# RC_Transmitter_TX_v43.net
KiCad netlist of a schematic drawn in EAGLE
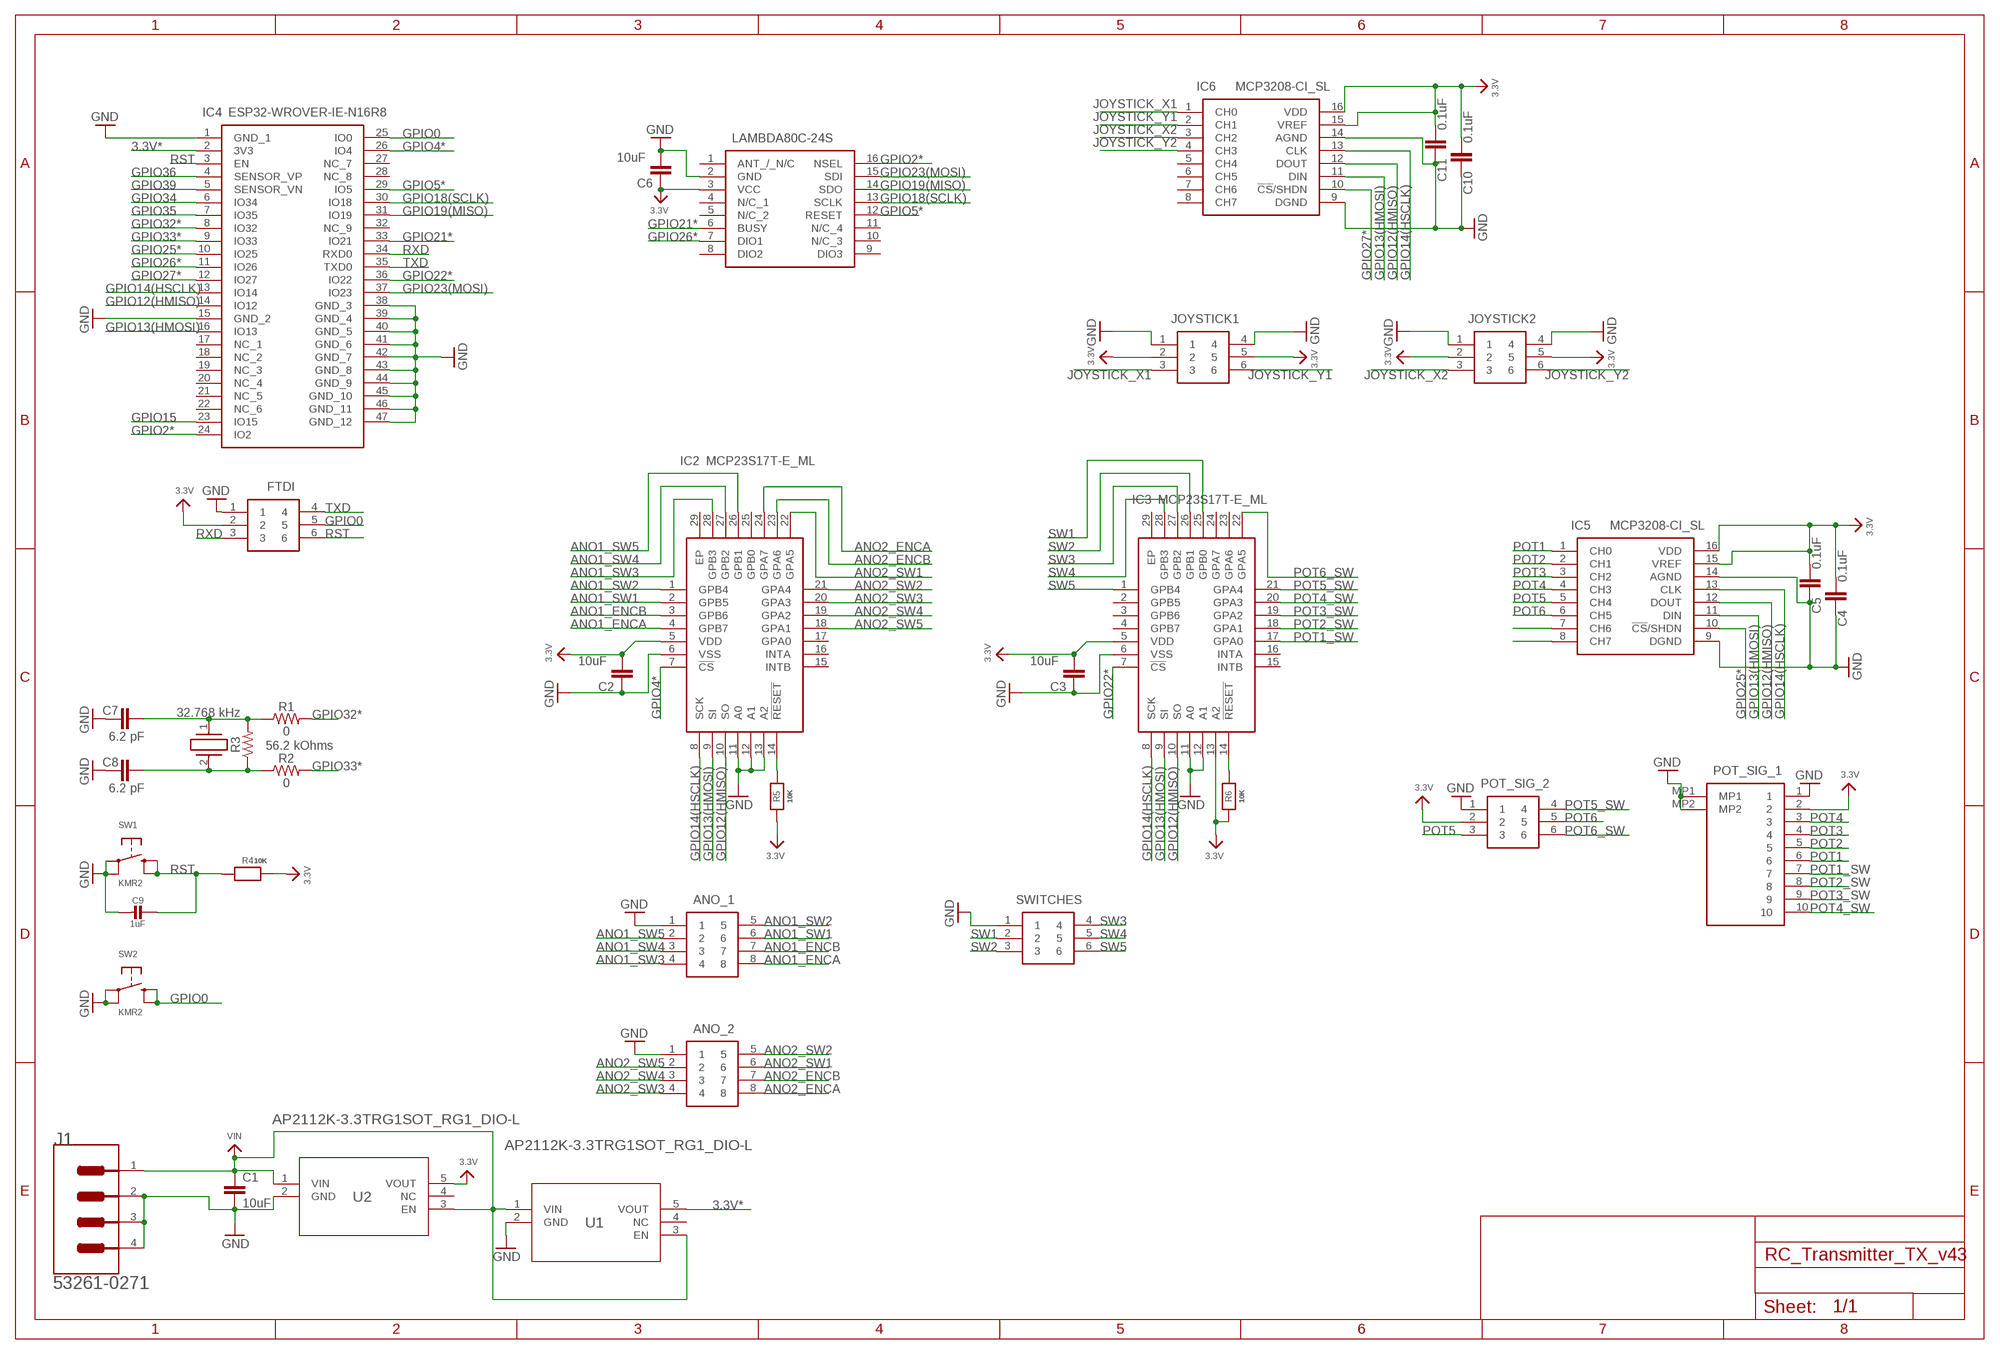
[diagram p0: schematic, sheet 1]

(export (version "E")
  (design (tool "Eeschema 10.0.6"))
  (components
    (comp (ref "ANO_1")
      (value "0532610871")
      (footprint "eagle-import:53261-0871")
      (libsource (lib "eagle-import") (part "0532610871"))
    )
    (comp (ref "ANO_2")
      (value "0532610871")
      (footprint "eagle-import:53261-0871")
      (libsource (lib "eagle-import") (part "0532610871"))
    )
    (comp (ref "C1")
      (value "10uF")
      (footprint "eagle-import:0805")
      (libsource (lib "eagle-import") (part "10UF-0805-10V-10%"))
    )
    (comp (ref "C2")
      (value "10uF")
      (footprint "eagle-import:0805")
      (libsource (lib "eagle-import") (part "10UF-0805-10V-10%"))
    )
    (comp (ref "C3")
      (value "10uF")
      (footprint "eagle-import:0805")
      (libsource (lib "eagle-import") (part "10UF-0805-10V-10%"))
    )
    (comp (ref "C4")
      (value "0.1uF")
      (footprint "eagle-import:0805")
      (libsource (lib "eagle-import") (part "10UF-0805-10V-10%"))
    )
    (comp (ref "C5")
      (value "0.1uF")
      (footprint "eagle-import:0805")
      (libsource (lib "eagle-import") (part "10UF-0805-10V-10%"))
    )
    (comp (ref "C6")
      (value "10uF")
      (footprint "eagle-import:0805")
      (libsource (lib "eagle-import") (part "10UF-0805-10V-10%"))
    )
    (comp (ref "C7")
      (value "6.2 pF")
      (footprint "eagle-import:CAPC2012X110")
      (libsource (lib "eagle-import") (part "CCHIP-0805(2012-METRIC)_"))
    )
    (comp (ref "C8")
      (value "6.2 pF")
      (footprint "eagle-import:CAPC2012X110")
      (libsource (lib "eagle-import") (part "CCHIP-0805(2012-METRIC)_"))
    )
    (comp (ref "C9")
      (value "1uF")
      (footprint "eagle-import:0805-NO")
      (libsource (lib "eagle-import") (part "CAP_CERAMIC0805-NOOUTLINE"))
    )
    (comp (ref "C10")
      (value "0.1uF")
      (footprint "eagle-import:0805")
      (libsource (lib "eagle-import") (part "10UF-0805-10V-10%"))
    )
    (comp (ref "C11")
      (value "0.1uF")
      (footprint "eagle-import:0805")
      (libsource (lib "eagle-import") (part "10UF-0805-10V-10%"))
    )
    (comp (ref "CRYSTAL")
      (value "32.768 kHz")
      (footprint "eagle-import:ECX327CDX1293")
      (fields
        (field (name "ARROW_PART_NUMBER") "ECX-.327-CDX-1293")
        (field (name "MOUSER_PART_NUMBER") "520-ECX-.327CDX-1293")
        (field (name "ARROW_PART_NUMBER_1") "Crystal")
      )
      (libsource (lib "eagle-import") (part "ECX-.327-CDX-1293"))
    )
    (comp (ref "FTDI")
      (value "0532610671")
      (footprint "eagle-import:0532610671")
      (libsource (lib "eagle-import") (part "0532610671"))
    )
    (comp (ref "IC1")
      (value "LAMBDA80C-24S")
      (footprint "eagle-import:LAMBDA80C24S")
      (fields (field (name "MOUSER_PART_NUMBER") "223-LAMBDA80C-24S"))
      (libsource (lib "eagle-import") (part "LAMBDA80C-24S"))
    )
    (comp (ref "IC2")
      (value "MCP23S17T-E_ML")
      (footprint "eagle-import:QFN65P600X600X100-29N")
      (fields
        (field (name "ARROW_PART_NUMBER") "MCP23S17T-E/ML")
        (field (name "MOUSER_PART_NUMBER") "579-MCP23S17T-E/ML")
      )
      (libsource (lib "eagle-import") (part "MCP23S17T-E_ML"))
    )
    (comp (ref "IC3")
      (value "MCP23S17T-E_ML")
      (footprint "eagle-import:QFN65P600X600X100-29N")
      (fields
        (field (name "ARROW_PART_NUMBER") "MCP23S17T-E/ML")
        (field (name "MOUSER_PART_NUMBER") "579-MCP23S17T-E/ML")
      )
      (libsource (lib "eagle-import") (part "MCP23S17T-E_ML"))
    )
    (comp (ref "IC4")
      (value "ESP32-WROVER-IE-N16R8")
      (footprint "eagle-import:ESP32WROVERIEN16R8")
      (fields
        (field (name "MANUFACTURER_PART_NUMBER") "ESP32-Wrover-IE-N16R8")
        (field (name "MOUSER_PART_NUMBER") "356-ESP32WRVIE2864UC")
      )
      (libsource (lib "eagle-import") (part "ESP32-WROVER-IE-N16R8"))
    )
    (comp (ref "IC5")
      (value "MCP3208-CI_SL")
      (footprint "eagle-import:SOIC127P600X175-16N")
      (fields
        (field (name "ARROW_PART_NUMBER") "MCP3208-CI/SL")
        (field (name "MOUSER_PART_NUMBER") "579-MCP3208CISL")
      )
      (libsource (lib "eagle-import") (part "MCP3208-CI_SL"))
    )
    (comp (ref "IC6")
      (value "MCP3208-CI_SL")
      (footprint "eagle-import:SOIC127P600X175-16N")
      (fields
        (field (name "ARROW_PART_NUMBER") "MCP3208-CI/SL")
        (field (name "MOUSER_PART_NUMBER") "579-MCP3208CISL")
      )
      (libsource (lib "eagle-import") (part "MCP3208-CI_SL"))
    )
    (comp (ref "J1")
      (value "MOLEX_53261-0271MOLEX_53261-0271_0_0")
      (footprint "eagle-import:MOLEX_53261-0271_0")
      (fields
        (field (name "DIGIKEY_PART_NUMBER") "WM7620CT-ND")
        (field (name "MF") "Molex")
        (field (name "MOUSER_PART_NUMBER") "538-53261-0271")
      )
      (libsource (lib "eagle-import") (part "MOLEX_53261-0271MOLEX_53261-0271_0_0"))
    )
    (comp (ref "JOYSTICK1")
      (value "0532610671")
      (footprint "eagle-import:0532610671")
      (libsource (lib "eagle-import") (part "0532610671"))
    )
    (comp (ref "JOYSTICK2")
      (value "0532610671")
      (footprint "eagle-import:0532610671")
      (libsource (lib "eagle-import") (part "0532610671"))
    )
    (comp (ref "POT_SIG_1")
      (value "0532611071")
      (footprint "eagle-import:0532611071")
      (libsource (lib "eagle-import") (part "0532611071"))
    )
    (comp (ref "POT_SIG_2")
      (value "0532610671")
      (footprint "eagle-import:0532610671")
      (libsource (lib "eagle-import") (part "0532610671"))
    )
    (comp (ref "R1")
      (value "0")
      (footprint "eagle-import:0603")
      (libsource (lib "eagle-import") (part "0OHM-0603-1/10W-5%"))
    )
    (comp (ref "R2")
      (value "0")
      (footprint "eagle-import:0603")
      (libsource (lib "eagle-import") (part "0OHM-0603-1/10W-5%"))
    )
    (comp (ref "R3")
      (value "56.2 kOhms")
      (footprint "eagle-import:0603")
      (libsource (lib "eagle-import") (part "0OHM-0603-1/10W-5%"))
    )
    (comp (ref "R4")
      (value "10K")
      (footprint "eagle-import:_0805")
      (libsource (lib "eagle-import") (part "RESISTOR_0805"))
    )
    (comp (ref "R5")
      (value "10K")
      (footprint "eagle-import:_0805")
      (libsource (lib "eagle-import") (part "RESISTOR_0805"))
    )
    (comp (ref "R6")
      (value "10K")
      (footprint "eagle-import:_0805")
      (libsource (lib "eagle-import") (part "RESISTOR_0805"))
    )
    (comp (ref "SW1")
      (value "KMR2")
      (footprint "eagle-import:BTN_KMR2_4.6X2.8")
      (libsource (lib "eagle-import") (part "SWITCH_TACT_SMT4.6X2.8"))
    )
    (comp (ref "SW2")
      (value "KMR2")
      (footprint "eagle-import:BTN_KMR2_4.6X2.8")
      (libsource (lib "eagle-import") (part "SWITCH_TACT_SMT4.6X2.8"))
    )
    (comp (ref "SWITCHES")
      (value "0532610671")
      (footprint "eagle-import:0532610671")
      (libsource (lib "eagle-import") (part "0532610671"))
    )
    (comp (ref "U1")
      (value "AP2112K-3.3TRG1SOT_RG1_DIO-L")
      (footprint "eagle-import:SOT_RG1_DIO-L")
      (fields
        (field (name "MANUFACTURER_PART_NUMBER") "AP2112K-3.3TRG1")
        (field (name "COPYRIGHT") "Copyright (C) 2023 Ultra Librarian. All rights reserved.")
      )
      (libsource (lib "eagle-import") (part "AP2112K-3.3TRG1SOT_RG1_DIO-L"))
    )
    (comp (ref "U2")
      (value "AP2112K-3.3TRG1SOT_RG1_DIO-L")
      (footprint "eagle-import:SOT_RG1_DIO-L")
      (fields
        (field (name "MANUFACTURER_PART_NUMBER") "AP2112K-3.3TRG1")
        (field (name "COPYRIGHT") "Copyright (C) 2023 Ultra Librarian. All rights reserved.")
      )
      (libsource (lib "eagle-import") (part "AP2112K-3.3TRG1SOT_RG1_DIO-L"))
    )
  )
  (nets
    (net (code "1") (name "/3.3V*") (class "Default")
      (node (ref "IC4") (pin "2") (pinfunction "3V3_2") (pintype "bidirectional"))
      (node (ref "U1") (pin "5") (pinfunction "VOUT_5") (pintype "passive"))
    )
    (net (code "2") (name "/ANO1_ENCA") (class "Default")
      (node (ref "ANO_1") (pin "8") (pinfunction "8_8") (pintype "bidirectional"))
      (node (ref "IC2") (pin "4") (pinfunction "GPB7_4") (pintype "bidirectional"))
    )
    (net (code "3") (name "/ANO1_ENCB") (class "Default")
      (node (ref "ANO_1") (pin "7") (pinfunction "7_7") (pintype "bidirectional"))
      (node (ref "IC2") (pin "3") (pinfunction "GPB6_3") (pintype "bidirectional"))
    )
    (net (code "4") (name "/ANO1_SW1") (class "Default")
      (node (ref "ANO_1") (pin "6") (pinfunction "6_6") (pintype "bidirectional"))
      (node (ref "IC2") (pin "2") (pinfunction "GPB5_2") (pintype "bidirectional"))
    )
    (net (code "5") (name "/ANO1_SW2") (class "Default")
      (node (ref "ANO_1") (pin "5") (pinfunction "5_5") (pintype "bidirectional"))
      (node (ref "IC2") (pin "1") (pinfunction "GPB4_1") (pintype "bidirectional"))
    )
    (net (code "6") (name "/ANO1_SW3") (class "Default")
      (node (ref "ANO_1") (pin "4") (pinfunction "4_4") (pintype "bidirectional"))
      (node (ref "IC2") (pin "28") (pinfunction "GPB3_28") (pintype "bidirectional"))
    )
    (net (code "7") (name "/ANO1_SW4") (class "Default")
      (node (ref "ANO_1") (pin "3") (pinfunction "3_3") (pintype "bidirectional"))
      (node (ref "IC2") (pin "27") (pinfunction "GPB2_27") (pintype "bidirectional"))
    )
    (net (code "8") (name "/ANO1_SW5") (class "Default")
      (node (ref "ANO_1") (pin "2") (pinfunction "2_2") (pintype "bidirectional"))
      (node (ref "IC2") (pin "26") (pinfunction "GPB1_26") (pintype "bidirectional"))
    )
    (net (code "9") (name "/ANO2_ENCA") (class "Default")
      (node (ref "ANO_2") (pin "8") (pinfunction "8_8") (pintype "bidirectional"))
      (node (ref "IC2") (pin "24") (pinfunction "GPA7_24") (pintype "bidirectional"))
    )
    (net (code "10") (name "/ANO2_ENCB") (class "Default")
      (node (ref "ANO_2") (pin "7") (pinfunction "7_7") (pintype "bidirectional"))
      (node (ref "IC2") (pin "23") (pinfunction "GPA6_23") (pintype "bidirectional"))
    )
    (net (code "11") (name "/ANO2_SW1") (class "Default")
      (node (ref "ANO_2") (pin "6") (pinfunction "6_6") (pintype "bidirectional"))
      (node (ref "IC2") (pin "22") (pinfunction "GPA5_22") (pintype "bidirectional"))
    )
    (net (code "12") (name "/ANO2_SW2") (class "Default")
      (node (ref "ANO_2") (pin "5") (pinfunction "5_5") (pintype "bidirectional"))
      (node (ref "IC2") (pin "21") (pinfunction "GPA4_21") (pintype "bidirectional"))
    )
    (net (code "13") (name "/ANO2_SW3") (class "Default")
      (node (ref "ANO_2") (pin "4") (pinfunction "4_4") (pintype "bidirectional"))
      (node (ref "IC2") (pin "20") (pinfunction "GPA3_20") (pintype "bidirectional"))
    )
    (net (code "14") (name "/ANO2_SW4") (class "Default")
      (node (ref "ANO_2") (pin "3") (pinfunction "3_3") (pintype "bidirectional"))
      (node (ref "IC2") (pin "19") (pinfunction "GPA2_19") (pintype "bidirectional"))
    )
    (net (code "15") (name "/ANO2_SW5") (class "Default")
      (node (ref "ANO_2") (pin "2") (pinfunction "2_2") (pintype "bidirectional"))
      (node (ref "IC2") (pin "18") (pinfunction "GPA1_18") (pintype "bidirectional"))
    )
    (net (code "16") (name "/GPIO0") (class "Default")
      (node (ref "FTDI") (pin "5") (pinfunction "5_5") (pintype "bidirectional"))
      (node (ref "IC4") (pin "25") (pinfunction "IO0_25") (pintype "bidirectional"))
      (node (ref "SW2") (pin "B") (pinfunction "S_B") (pintype "passive"))
      (node (ref "SW2") (pin "B'") (pinfunction "S1_B'") (pintype "passive"))
    )
    (net (code "17") (name "/GPIO2*") (class "Default")
      (node (ref "IC1") (pin "16") (pinfunction "NSEL_16") (pintype "bidirectional"))
      (node (ref "IC4") (pin "24") (pinfunction "IO2_24") (pintype "bidirectional"))
    )
    (net (code "18") (name "/GPIO4*") (class "Default")
      (node (ref "IC2") (pin "7") (pinfunction "~{CS}_7") (pintype "bidirectional"))
      (node (ref "IC4") (pin "26") (pinfunction "IO4_26") (pintype "bidirectional"))
    )
    (net (code "19") (name "/GPIO5*") (class "Default")
      (node (ref "IC1") (pin "12") (pinfunction "RESET_12") (pintype "bidirectional"))
      (node (ref "IC4") (pin "29") (pinfunction "IO5_29") (pintype "bidirectional"))
    )
    (net (code "20") (name "/GPIO12(HMISO)") (class "Default")
      (node (ref "IC2") (pin "10") (pinfunction "SO_10") (pintype "bidirectional"))
      (node (ref "IC3") (pin "10") (pinfunction "SO_10") (pintype "bidirectional"))
      (node (ref "IC4") (pin "14") (pinfunction "IO12_14") (pintype "bidirectional"))
      (node (ref "IC5") (pin "12") (pinfunction "DOUT_12") (pintype "bidirectional"))
      (node (ref "IC6") (pin "12") (pinfunction "DOUT_12") (pintype "bidirectional"))
    )
    (net (code "21") (name "/GPIO13(HMOSI)") (class "Default")
      (node (ref "IC2") (pin "9") (pinfunction "SI_9") (pintype "bidirectional"))
      (node (ref "IC3") (pin "9") (pinfunction "SI_9") (pintype "bidirectional"))
      (node (ref "IC4") (pin "16") (pinfunction "IO13_16") (pintype "bidirectional"))
      (node (ref "IC5") (pin "11") (pinfunction "DIN_11") (pintype "bidirectional"))
      (node (ref "IC6") (pin "11") (pinfunction "DIN_11") (pintype "bidirectional"))
    )
    (net (code "22") (name "/GPIO14(HSCLK)") (class "Default")
      (node (ref "IC2") (pin "8") (pinfunction "SCK_8") (pintype "bidirectional"))
      (node (ref "IC3") (pin "8") (pinfunction "SCK_8") (pintype "bidirectional"))
      (node (ref "IC4") (pin "13") (pinfunction "IO14_13") (pintype "bidirectional"))
      (node (ref "IC5") (pin "13") (pinfunction "CLK_13") (pintype "bidirectional"))
      (node (ref "IC6") (pin "13") (pinfunction "CLK_13") (pintype "bidirectional"))
    )
    (net (code "23") (name "/GPIO15") (class "Default")
      (node (ref "IC4") (pin "23") (pinfunction "IO15_23") (pintype "bidirectional"))
    )
    (net (code "24") (name "/GPIO18(SCLK)") (class "Default")
      (node (ref "IC1") (pin "13") (pinfunction "SCLK_13") (pintype "bidirectional"))
      (node (ref "IC4") (pin "30") (pinfunction "IO18_30") (pintype "bidirectional"))
    )
    (net (code "25") (name "/GPIO19(MISO)") (class "Default")
      (node (ref "IC1") (pin "14") (pinfunction "SDO_14") (pintype "bidirectional"))
      (node (ref "IC4") (pin "31") (pinfunction "IO19_31") (pintype "bidirectional"))
    )
    (net (code "26") (name "/GPIO21*") (class "Default")
      (node (ref "IC1") (pin "6") (pinfunction "BUSY_6") (pintype "bidirectional"))
      (node (ref "IC4") (pin "33") (pinfunction "IO21_33") (pintype "bidirectional"))
    )
    (net (code "27") (name "/GPIO22*") (class "Default")
      (node (ref "IC3") (pin "7") (pinfunction "~{CS}_7") (pintype "bidirectional"))
      (node (ref "IC4") (pin "36") (pinfunction "IO22_36") (pintype "bidirectional"))
    )
    (net (code "28") (name "/GPIO23(MOSI)") (class "Default")
      (node (ref "IC1") (pin "15") (pinfunction "SDI_15") (pintype "bidirectional"))
      (node (ref "IC4") (pin "37") (pinfunction "IO23_37") (pintype "bidirectional"))
    )
    (net (code "29") (name "/GPIO25*") (class "Default")
      (node (ref "IC4") (pin "10") (pinfunction "IO25_10") (pintype "bidirectional"))
      (node (ref "IC5") (pin "10") (pinfunction "~{CS}/SHDN_10") (pintype "bidirectional"))
    )
    (net (code "30") (name "/GPIO26*") (class "Default")
      (node (ref "IC1") (pin "7") (pinfunction "DIO1_7") (pintype "bidirectional"))
      (node (ref "IC4") (pin "11") (pinfunction "IO26_11") (pintype "bidirectional"))
    )
    (net (code "31") (name "/GPIO27*") (class "Default")
      (node (ref "IC4") (pin "12") (pinfunction "IO27_12") (pintype "bidirectional"))
      (node (ref "IC6") (pin "10") (pinfunction "~{CS}/SHDN_10") (pintype "bidirectional"))
    )
    (net (code "32") (name "/GPIO32*") (class "Default")
      (node (ref "IC4") (pin "8") (pinfunction "IO32_8") (pintype "bidirectional"))
      (node (ref "R1") (pin "2") (pinfunction "2_2") (pintype "passive"))
    )
    (net (code "33") (name "/GPIO33*") (class "Default")
      (node (ref "IC4") (pin "9") (pinfunction "IO33_9") (pintype "bidirectional"))
      (node (ref "R2") (pin "2") (pinfunction "2_2") (pintype "passive"))
    )
    (net (code "34") (name "/GPIO34") (class "Default")
      (node (ref "IC4") (pin "6") (pinfunction "IO34_6") (pintype "bidirectional"))
    )
    (net (code "35") (name "/GPIO35") (class "Default")
      (node (ref "IC4") (pin "7") (pinfunction "IO35_7") (pintype "bidirectional"))
    )
    (net (code "36") (name "/GPIO36") (class "Default")
      (node (ref "IC4") (pin "4") (pinfunction "SENSOR_VP_4") (pintype "bidirectional"))
    )
    (net (code "37") (name "/GPIO39") (class "Default")
      (node (ref "IC4") (pin "5") (pinfunction "SENSOR_VN_5") (pintype "bidirectional"))
    )
    (net (code "38") (name "/JOYSTICK_X1") (class "Default")
      (node (ref "IC6") (pin "1") (pinfunction "CH0_1") (pintype "bidirectional"))
      (node (ref "JOYSTICK1") (pin "3") (pinfunction "3_3") (pintype "bidirectional"))
    )
    (net (code "39") (name "/JOYSTICK_X2") (class "Default")
      (node (ref "IC6") (pin "3") (pinfunction "CH2_3") (pintype "bidirectional"))
      (node (ref "JOYSTICK2") (pin "3") (pinfunction "3_3") (pintype "bidirectional"))
    )
    (net (code "40") (name "/JOYSTICK_Y1") (class "Default")
      (node (ref "IC6") (pin "2") (pinfunction "CH1_2") (pintype "bidirectional"))
      (node (ref "JOYSTICK1") (pin "6") (pinfunction "6_6") (pintype "bidirectional"))
    )
    (net (code "41") (name "/JOYSTICK_Y2") (class "Default")
      (node (ref "IC6") (pin "4") (pinfunction "CH3_4") (pintype "bidirectional"))
      (node (ref "JOYSTICK2") (pin "6") (pinfunction "6_6") (pintype "bidirectional"))
    )
    (net (code "42") (name "/POT1") (class "Default")
      (node (ref "IC5") (pin "1") (pinfunction "CH0_1") (pintype "bidirectional"))
      (node (ref "POT_SIG_1") (pin "6") (pinfunction "6_6") (pintype "bidirectional"))
    )
    (net (code "43") (name "/POT1_SW") (class "Default")
      (node (ref "IC3") (pin "17") (pinfunction "GPA0_17") (pintype "bidirectional"))
      (node (ref "POT_SIG_1") (pin "7") (pinfunction "7_7") (pintype "bidirectional"))
    )
    (net (code "44") (name "/POT2") (class "Default")
      (node (ref "IC5") (pin "2") (pinfunction "CH1_2") (pintype "bidirectional"))
      (node (ref "POT_SIG_1") (pin "5") (pinfunction "5_5") (pintype "bidirectional"))
    )
    (net (code "45") (name "/POT2_SW") (class "Default")
      (node (ref "IC3") (pin "18") (pinfunction "GPA1_18") (pintype "bidirectional"))
      (node (ref "POT_SIG_1") (pin "8") (pinfunction "8_8") (pintype "bidirectional"))
    )
    (net (code "46") (name "/POT3") (class "Default")
      (node (ref "IC5") (pin "3") (pinfunction "CH2_3") (pintype "bidirectional"))
      (node (ref "POT_SIG_1") (pin "4") (pinfunction "4_4") (pintype "bidirectional"))
    )
    (net (code "47") (name "/POT3_SW") (class "Default")
      (node (ref "IC3") (pin "19") (pinfunction "GPA2_19") (pintype "bidirectional"))
      (node (ref "POT_SIG_1") (pin "9") (pinfunction "9_9") (pintype "bidirectional"))
    )
    (net (code "48") (name "/POT4") (class "Default")
      (node (ref "IC5") (pin "4") (pinfunction "CH3_4") (pintype "bidirectional"))
      (node (ref "POT_SIG_1") (pin "3") (pinfunction "3_3") (pintype "bidirectional"))
    )
    (net (code "49") (name "/POT4_SW") (class "Default")
      (node (ref "IC3") (pin "20") (pinfunction "GPA3_20") (pintype "bidirectional"))
      (node (ref "POT_SIG_1") (pin "10") (pinfunction "10_10") (pintype "bidirectional"))
    )
    (net (code "50") (name "/POT5") (class "Default")
      (node (ref "IC5") (pin "5") (pinfunction "CH4_5") (pintype "bidirectional"))
      (node (ref "POT_SIG_2") (pin "3") (pinfunction "3_3") (pintype "bidirectional"))
    )
    (net (code "51") (name "/POT5_SW") (class "Default")
      (node (ref "IC3") (pin "21") (pinfunction "GPA4_21") (pintype "bidirectional"))
      (node (ref "POT_SIG_2") (pin "4") (pinfunction "4_4") (pintype "bidirectional"))
    )
    (net (code "52") (name "/POT6") (class "Default")
      (node (ref "IC5") (pin "6") (pinfunction "CH5_6") (pintype "bidirectional"))
      (node (ref "POT_SIG_2") (pin "5") (pinfunction "5_5") (pintype "bidirectional"))
    )
    (net (code "53") (name "/POT6_SW") (class "Default")
      (node (ref "IC3") (pin "22") (pinfunction "GPA5_22") (pintype "bidirectional"))
      (node (ref "POT_SIG_2") (pin "6") (pinfunction "6_6") (pintype "bidirectional"))
    )
    (net (code "54") (name "/RST") (class "Default")
      (node (ref "C9") (pin "1") (pinfunction "1_1") (pintype "passive"))
      (node (ref "FTDI") (pin "6") (pinfunction "6_6") (pintype "bidirectional"))
      (node (ref "IC4") (pin "3") (pinfunction "EN_3") (pintype "bidirectional"))
      (node (ref "R4") (pin "1") (pinfunction "1_1") (pintype "passive"))
      (node (ref "SW1") (pin "B") (pinfunction "S_B") (pintype "passive"))
      (node (ref "SW1") (pin "B'") (pinfunction "S1_B'") (pintype "passive"))
    )
    (net (code "55") (name "/RXD") (class "Default")
      (node (ref "FTDI") (pin "3") (pinfunction "3_3") (pintype "bidirectional"))
      (node (ref "IC4") (pin "34") (pinfunction "RXD0_34") (pintype "bidirectional"))
    )
    (net (code "56") (name "/SW1") (class "Default")
      (node (ref "IC3") (pin "25") (pinfunction "GPB0_25") (pintype "bidirectional"))
      (node (ref "SWITCHES") (pin "2") (pinfunction "2_2") (pintype "bidirectional"))
    )
    (net (code "57") (name "/SW2") (class "Default")
      (node (ref "IC3") (pin "26") (pinfunction "GPB1_26") (pintype "bidirectional"))
      (node (ref "SWITCHES") (pin "3") (pinfunction "3_3") (pintype "bidirectional"))
    )
    (net (code "58") (name "/SW3") (class "Default")
      (node (ref "IC3") (pin "27") (pinfunction "GPB2_27") (pintype "bidirectional"))
      (node (ref "SWITCHES") (pin "4") (pinfunction "4_4") (pintype "bidirectional"))
    )
    (net (code "59") (name "/SW4") (class "Default")
      (node (ref "IC3") (pin "28") (pinfunction "GPB3_28") (pintype "bidirectional"))
      (node (ref "SWITCHES") (pin "5") (pinfunction "5_5") (pintype "bidirectional"))
    )
    (net (code "60") (name "/SW5") (class "Default")
      (node (ref "IC3") (pin "1") (pinfunction "GPB4_1") (pintype "bidirectional"))
      (node (ref "SWITCHES") (pin "6") (pinfunction "6_6") (pintype "bidirectional"))
    )
    (net (code "61") (name "/TXD") (class "Default")
      (node (ref "FTDI") (pin "4") (pinfunction "4_4") (pintype "bidirectional"))
      (node (ref "IC4") (pin "35") (pinfunction "TXD0_35") (pintype "bidirectional"))
    )
    (net (code "62") (name "3.3V") (class "Default")
      (node (ref "C10") (pin "2") (pinfunction "2_2") (pintype "passive"))
      (node (ref "C11") (pin "2") (pinfunction "2_2") (pintype "passive"))
      (node (ref "C2") (pin "2") (pinfunction "2_2") (pintype "passive"))
      (node (ref "C3") (pin "2") (pinfunction "2_2") (pintype "passive"))
      (node (ref "C4") (pin "2") (pinfunction "2_2") (pintype "passive"))
      (node (ref "C5") (pin "2") (pinfunction "2_2") (pintype "passive"))
      (node (ref "C6") (pin "1") (pinfunction "1_1") (pintype "passive"))
      (node (ref "FTDI") (pin "2") (pinfunction "2_2") (pintype "bidirectional"))
      (node (ref "IC1") (pin "3") (pinfunction "VCC_3") (pintype "bidirectional"))
      (node (ref "IC2") (pin "5") (pinfunction "VDD_5") (pintype "bidirectional"))
      (node (ref "IC3") (pin "13") (pinfunction "A2_13") (pintype "bidirectional"))
      (node (ref "IC3") (pin "5") (pinfunction "VDD_5") (pintype "bidirectional"))
      (node (ref "IC5") (pin "15") (pinfunction "VREF_15") (pintype "bidirectional"))
      (node (ref "IC5") (pin "16") (pinfunction "VDD_16") (pintype "bidirectional"))
      (node (ref "IC6") (pin "15") (pinfunction "VREF_15") (pintype "bidirectional"))
      (node (ref "IC6") (pin "16") (pinfunction "VDD_16") (pintype "bidirectional"))
      (node (ref "JOYSTICK1") (pin "2") (pinfunction "2_2") (pintype "bidirectional"))
      (node (ref "JOYSTICK1") (pin "5") (pinfunction "5_5") (pintype "bidirectional"))
      (node (ref "JOYSTICK2") (pin "2") (pinfunction "2_2") (pintype "bidirectional"))
      (node (ref "JOYSTICK2") (pin "5") (pinfunction "5_5") (pintype "bidirectional"))
      (node (ref "POT_SIG_1") (pin "2") (pinfunction "2_2") (pintype "bidirectional"))
      (node (ref "POT_SIG_2") (pin "2") (pinfunction "2_2") (pintype "bidirectional"))
      (node (ref "R4") (pin "2") (pinfunction "2_2") (pintype "passive"))
      (node (ref "R5") (pin "1") (pinfunction "1_1") (pintype "passive"))
      (node (ref "R6") (pin "1") (pinfunction "1_1") (pintype "passive"))
      (node (ref "U2") (pin "5") (pinfunction "VOUT_5") (pintype "passive"))
    )
    (net (code "63") (name "GND") (class "Default")
      (node (ref "ANO_1") (pin "1") (pinfunction "1_1") (pintype "bidirectional"))
      (node (ref "ANO_2") (pin "1") (pinfunction "1_1") (pintype "bidirectional"))
      (node (ref "C1") (pin "2") (pinfunction "2_2") (pintype "passive"))
      (node (ref "C10") (pin "1") (pinfunction "1_1") (pintype "passive"))
      (node (ref "C11") (pin "1") (pinfunction "1_1") (pintype "passive"))
      (node (ref "C2") (pin "1") (pinfunction "1_1") (pintype "passive"))
      (node (ref "C3") (pin "1") (pinfunction "1_1") (pintype "passive"))
      (node (ref "C4") (pin "1") (pinfunction "1_1") (pintype "passive"))
      (node (ref "C5") (pin "1") (pinfunction "1_1") (pintype "passive"))
      (node (ref "C6") (pin "2") (pinfunction "2_2") (pintype "passive"))
      (node (ref "C7") (pin "1") (pinfunction "1_1") (pintype "passive"))
      (node (ref "C8") (pin "1") (pinfunction "1_1") (pintype "passive"))
      (node (ref "C9") (pin "2") (pinfunction "2_2") (pintype "passive"))
      (node (ref "FTDI") (pin "1") (pinfunction "1_1") (pintype "bidirectional"))
      (node (ref "IC1") (pin "2") (pinfunction "GND_2") (pintype "bidirectional"))
      (node (ref "IC2") (pin "11") (pinfunction "A0_11") (pintype "bidirectional"))
      (node (ref "IC2") (pin "12") (pinfunction "A1_12") (pintype "bidirectional"))
      (node (ref "IC2") (pin "13") (pinfunction "A2_13") (pintype "bidirectional"))
      (node (ref "IC2") (pin "6") (pinfunction "VSS_6") (pintype "bidirectional"))
      (node (ref "IC3") (pin "11") (pinfunction "A0_11") (pintype "bidirectional"))
      (node (ref "IC3") (pin "12") (pinfunction "A1_12") (pintype "bidirectional"))
      (node (ref "IC3") (pin "6") (pinfunction "VSS_6") (pintype "bidirectional"))
      (node (ref "IC4") (pin "1") (pinfunction "GND_1_1") (pintype "bidirectional"))
      (node (ref "IC4") (pin "15") (pinfunction "GND_2_15") (pintype "bidirectional"))
      (node (ref "IC4") (pin "38") (pinfunction "GND_3_38") (pintype "bidirectional"))
      (node (ref "IC4") (pin "39") (pinfunction "GND_4_39") (pintype "bidirectional"))
      (node (ref "IC4") (pin "40") (pinfunction "GND_5_40") (pintype "bidirectional"))
      (node (ref "IC4") (pin "41") (pinfunction "GND_6_41") (pintype "bidirectional"))
      (node (ref "IC4") (pin "42") (pinfunction "GND_7_42") (pintype "bidirectional"))
      (node (ref "IC4") (pin "43") (pinfunction "GND_8_43") (pintype "bidirectional"))
      (node (ref "IC4") (pin "44") (pinfunction "GND_9_44") (pintype "bidirectional"))
      (node (ref "IC4") (pin "45") (pinfunction "GND_10_45") (pintype "bidirectional"))
      (node (ref "IC4") (pin "46") (pinfunction "GND_11_46") (pintype "bidirectional"))
      (node (ref "IC4") (pin "47") (pinfunction "GND_12_47") (pintype "bidirectional"))
      (node (ref "IC5") (pin "14") (pinfunction "AGND_14") (pintype "bidirectional"))
      (node (ref "IC5") (pin "9") (pinfunction "DGND_9") (pintype "bidirectional"))
      (node (ref "IC6") (pin "14") (pinfunction "AGND_14") (pintype "bidirectional"))
      (node (ref "IC6") (pin "9") (pinfunction "DGND_9") (pintype "bidirectional"))
      (node (ref "J1") (pin "2") (pinfunction "2_2") (pintype "bidirectional"))
      (node (ref "J1") (pin "3") (pinfunction "MNT_1_3") (pintype "bidirectional"))
      (node (ref "J1") (pin "4") (pinfunction "MNT_2_4") (pintype "bidirectional"))
      (node (ref "JOYSTICK1") (pin "1") (pinfunction "1_1") (pintype "bidirectional"))
      (node (ref "JOYSTICK1") (pin "4") (pinfunction "4_4") (pintype "bidirectional"))
      (node (ref "JOYSTICK2") (pin "1") (pinfunction "1_1") (pintype "bidirectional"))
      (node (ref "JOYSTICK2") (pin "4") (pinfunction "4_4") (pintype "bidirectional"))
      (node (ref "POT_SIG_1") (pin "1") (pinfunction "1_1") (pintype "bidirectional"))
      (node (ref "POT_SIG_1") (pin "MP1") (pinfunction "MP1_MP1") (pintype "bidirectional"))
      (node (ref "POT_SIG_1") (pin "MP2") (pinfunction "MP2_MP2") (pintype "bidirectional"))
      (node (ref "POT_SIG_2") (pin "1") (pinfunction "1_1") (pintype "bidirectional"))
      (node (ref "SW1") (pin "A") (pinfunction "P_A") (pintype "passive"))
      (node (ref "SW1") (pin "A'") (pinfunction "P1_A'") (pintype "passive"))
      (node (ref "SW2") (pin "A") (pinfunction "P_A") (pintype "passive"))
      (node (ref "SW2") (pin "A'") (pinfunction "P1_A'") (pintype "passive"))
      (node (ref "SWITCHES") (pin "1") (pinfunction "1_1") (pintype "bidirectional"))
      (node (ref "U1") (pin "2") (pinfunction "GND_2") (pintype "passive"))
      (node (ref "U2") (pin "2") (pinfunction "GND_2") (pintype "passive"))
    )
    (net (code "64") (name "Net-(CRYSTAL-X1)") (class "Default")
      (node (ref "C7") (pin "2") (pinfunction "2_2") (pintype "passive"))
      (node (ref "CRYSTAL") (pin "1") (pinfunction "X1_1") (pintype "bidirectional"))
      (node (ref "R1") (pin "1") (pinfunction "1_1") (pintype "passive"))
      (node (ref "R3") (pin "2") (pinfunction "2_2") (pintype "passive"))
    )
    (net (code "65") (name "Net-(CRYSTAL-X2)") (class "Default")
      (node (ref "C8") (pin "2") (pinfunction "2_2") (pintype "passive"))
      (node (ref "CRYSTAL") (pin "2") (pinfunction "X2_2") (pintype "bidirectional"))
      (node (ref "R2") (pin "1") (pinfunction "1_1") (pintype "passive"))
      (node (ref "R3") (pin "1") (pinfunction "1_1") (pintype "passive"))
    )
    (net (code "66") (name "Net-(IC2-~{RESET})") (class "Default")
      (node (ref "IC2") (pin "14") (pinfunction "~{RESET}_14") (pintype "bidirectional"))
      (node (ref "R5") (pin "2") (pinfunction "2_2") (pintype "passive"))
    )
    (net (code "67") (name "Net-(IC3-~{RESET})") (class "Default")
      (node (ref "IC3") (pin "14") (pinfunction "~{RESET}_14") (pintype "bidirectional"))
      (node (ref "R6") (pin "2") (pinfunction "2_2") (pintype "passive"))
    )
    (net (code "68") (name "VIN") (class "Default")
      (node (ref "C1") (pin "1") (pinfunction "1_1") (pintype "passive"))
      (node (ref "J1") (pin "1") (pinfunction "1_1") (pintype "bidirectional"))
      (node (ref "U1") (pin "1") (pinfunction "VIN_1") (pintype "passive"))
      (node (ref "U1") (pin "3") (pinfunction "EN_3") (pintype "passive"))
      (node (ref "U2") (pin "1") (pinfunction "VIN_1") (pintype "passive"))
      (node (ref "U2") (pin "3") (pinfunction "EN_3") (pintype "passive"))
    )
    (net (code "69") (name "unconnected-(IC1-ANT_{slash}_N{slash}C-Pad1)") (class "Default")
      (node (ref "IC1") (pin "1") (pinfunction "ANT_/_N/C_1") (pintype "bidirectional"))
    )
    (net (code "70") (name "unconnected-(IC1-DIO2-Pad8)") (class "Default")
      (node (ref "IC1") (pin "8") (pinfunction "DIO2_8") (pintype "bidirectional"))
    )
    (net (code "71") (name "unconnected-(IC1-DIO3-Pad9)") (class "Default")
      (node (ref "IC1") (pin "9") (pinfunction "DIO3_9") (pintype "bidirectional"))
    )
    (net (code "72") (name "unconnected-(IC1-N{slash}C_1-Pad4)") (class "Default")
      (node (ref "IC1") (pin "4") (pinfunction "N/C_1_4") (pintype "bidirectional"))
    )
    (net (code "73") (name "unconnected-(IC1-N{slash}C_2-Pad5)") (class "Default")
      (node (ref "IC1") (pin "5") (pinfunction "N/C_2_5") (pintype "bidirectional"))
    )
    (net (code "74") (name "unconnected-(IC1-N{slash}C_3-Pad10)") (class "Default")
      (node (ref "IC1") (pin "10") (pinfunction "N/C_3_10") (pintype "bidirectional"))
    )
    (net (code "75") (name "unconnected-(IC1-N{slash}C_4-Pad11)") (class "Default")
      (node (ref "IC1") (pin "11") (pinfunction "N/C_4_11") (pintype "bidirectional"))
    )
    (net (code "76") (name "unconnected-(IC2-EP-Pad29)") (class "Default")
      (node (ref "IC2") (pin "29") (pinfunction "EP_29") (pintype "bidirectional"))
    )
    (net (code "77") (name "unconnected-(IC2-GPA0-Pad17)") (class "Default")
      (node (ref "IC2") (pin "17") (pinfunction "GPA0_17") (pintype "bidirectional"))
    )
    (net (code "78") (name "unconnected-(IC2-GPB0-Pad25)") (class "Default")
      (node (ref "IC2") (pin "25") (pinfunction "GPB0_25") (pintype "bidirectional"))
    )
    (net (code "79") (name "unconnected-(IC2-INTA-Pad16)") (class "Default")
      (node (ref "IC2") (pin "16") (pinfunction "INTA_16") (pintype "bidirectional"))
    )
    (net (code "80") (name "unconnected-(IC2-INTB-Pad15)") (class "Default")
      (node (ref "IC2") (pin "15") (pinfunction "INTB_15") (pintype "bidirectional"))
    )
    (net (code "81") (name "unconnected-(IC3-EP-Pad29)") (class "Default")
      (node (ref "IC3") (pin "29") (pinfunction "EP_29") (pintype "bidirectional"))
    )
    (net (code "82") (name "unconnected-(IC3-GPA6-Pad23)") (class "Default")
      (node (ref "IC3") (pin "23") (pinfunction "GPA6_23") (pintype "bidirectional"))
    )
    (net (code "83") (name "unconnected-(IC3-GPA7-Pad24)") (class "Default")
      (node (ref "IC3") (pin "24") (pinfunction "GPA7_24") (pintype "bidirectional"))
    )
    (net (code "84") (name "unconnected-(IC3-GPB5-Pad2)") (class "Default")
      (node (ref "IC3") (pin "2") (pinfunction "GPB5_2") (pintype "bidirectional"))
    )
    (net (code "85") (name "unconnected-(IC3-GPB6-Pad3)") (class "Default")
      (node (ref "IC3") (pin "3") (pinfunction "GPB6_3") (pintype "bidirectional"))
    )
    (net (code "86") (name "unconnected-(IC3-GPB7-Pad4)") (class "Default")
      (node (ref "IC3") (pin "4") (pinfunction "GPB7_4") (pintype "bidirectional"))
    )
    (net (code "87") (name "unconnected-(IC3-INTA-Pad16)") (class "Default")
      (node (ref "IC3") (pin "16") (pinfunction "INTA_16") (pintype "bidirectional"))
    )
    (net (code "88") (name "unconnected-(IC3-INTB-Pad15)") (class "Default")
      (node (ref "IC3") (pin "15") (pinfunction "INTB_15") (pintype "bidirectional"))
    )
    (net (code "89") (name "unconnected-(IC4-NC_1-Pad17)") (class "Default")
      (node (ref "IC4") (pin "17") (pinfunction "NC_1_17") (pintype "bidirectional"))
    )
    (net (code "90") (name "unconnected-(IC4-NC_2-Pad18)") (class "Default")
      (node (ref "IC4") (pin "18") (pinfunction "NC_2_18") (pintype "bidirectional"))
    )
    (net (code "91") (name "unconnected-(IC4-NC_3-Pad19)") (class "Default")
      (node (ref "IC4") (pin "19") (pinfunction "NC_3_19") (pintype "bidirectional"))
    )
    (net (code "92") (name "unconnected-(IC4-NC_4-Pad20)") (class "Default")
      (node (ref "IC4") (pin "20") (pinfunction "NC_4_20") (pintype "bidirectional"))
    )
    (net (code "93") (name "unconnected-(IC4-NC_5-Pad21)") (class "Default")
      (node (ref "IC4") (pin "21") (pinfunction "NC_5_21") (pintype "bidirectional"))
    )
    (net (code "94") (name "unconnected-(IC4-NC_6-Pad22)") (class "Default")
      (node (ref "IC4") (pin "22") (pinfunction "NC_6_22") (pintype "bidirectional"))
    )
    (net (code "95") (name "unconnected-(IC4-NC_7-Pad27)") (class "Default")
      (node (ref "IC4") (pin "27") (pinfunction "NC_7_27") (pintype "bidirectional"))
    )
    (net (code "96") (name "unconnected-(IC4-NC_8-Pad28)") (class "Default")
      (node (ref "IC4") (pin "28") (pinfunction "NC_8_28") (pintype "bidirectional"))
    )
    (net (code "97") (name "unconnected-(IC4-NC_9-Pad32)") (class "Default")
      (node (ref "IC4") (pin "32") (pinfunction "NC_9_32") (pintype "bidirectional"))
    )
    (net (code "98") (name "unconnected-(IC5-CH6-Pad7)") (class "Default")
      (node (ref "IC5") (pin "7") (pinfunction "CH6_7") (pintype "bidirectional"))
    )
    (net (code "99") (name "unconnected-(IC5-CH7-Pad8)") (class "Default")
      (node (ref "IC5") (pin "8") (pinfunction "CH7_8") (pintype "bidirectional"))
    )
    (net (code "100") (name "unconnected-(IC6-CH4-Pad5)") (class "Default")
      (node (ref "IC6") (pin "5") (pinfunction "CH4_5") (pintype "bidirectional"))
    )
    (net (code "101") (name "unconnected-(IC6-CH5-Pad6)") (class "Default")
      (node (ref "IC6") (pin "6") (pinfunction "CH5_6") (pintype "bidirectional"))
    )
    (net (code "102") (name "unconnected-(IC6-CH6-Pad7)") (class "Default")
      (node (ref "IC6") (pin "7") (pinfunction "CH6_7") (pintype "bidirectional"))
    )
    (net (code "103") (name "unconnected-(IC6-CH7-Pad8)") (class "Default")
      (node (ref "IC6") (pin "8") (pinfunction "CH7_8") (pintype "bidirectional"))
    )
    (net (code "104") (name "unconnected-(U1-NC-Pad4)") (class "Default")
      (node (ref "U1") (pin "4") (pinfunction "NC_4") (pintype "passive"))
    )
    (net (code "105") (name "unconnected-(U2-NC-Pad4)") (class "Default")
      (node (ref "U2") (pin "4") (pinfunction "NC_4") (pintype "passive"))
    )
  )
)
